# Power_suply.net
KiCad netlist of a schematic drawn in Altium Designer
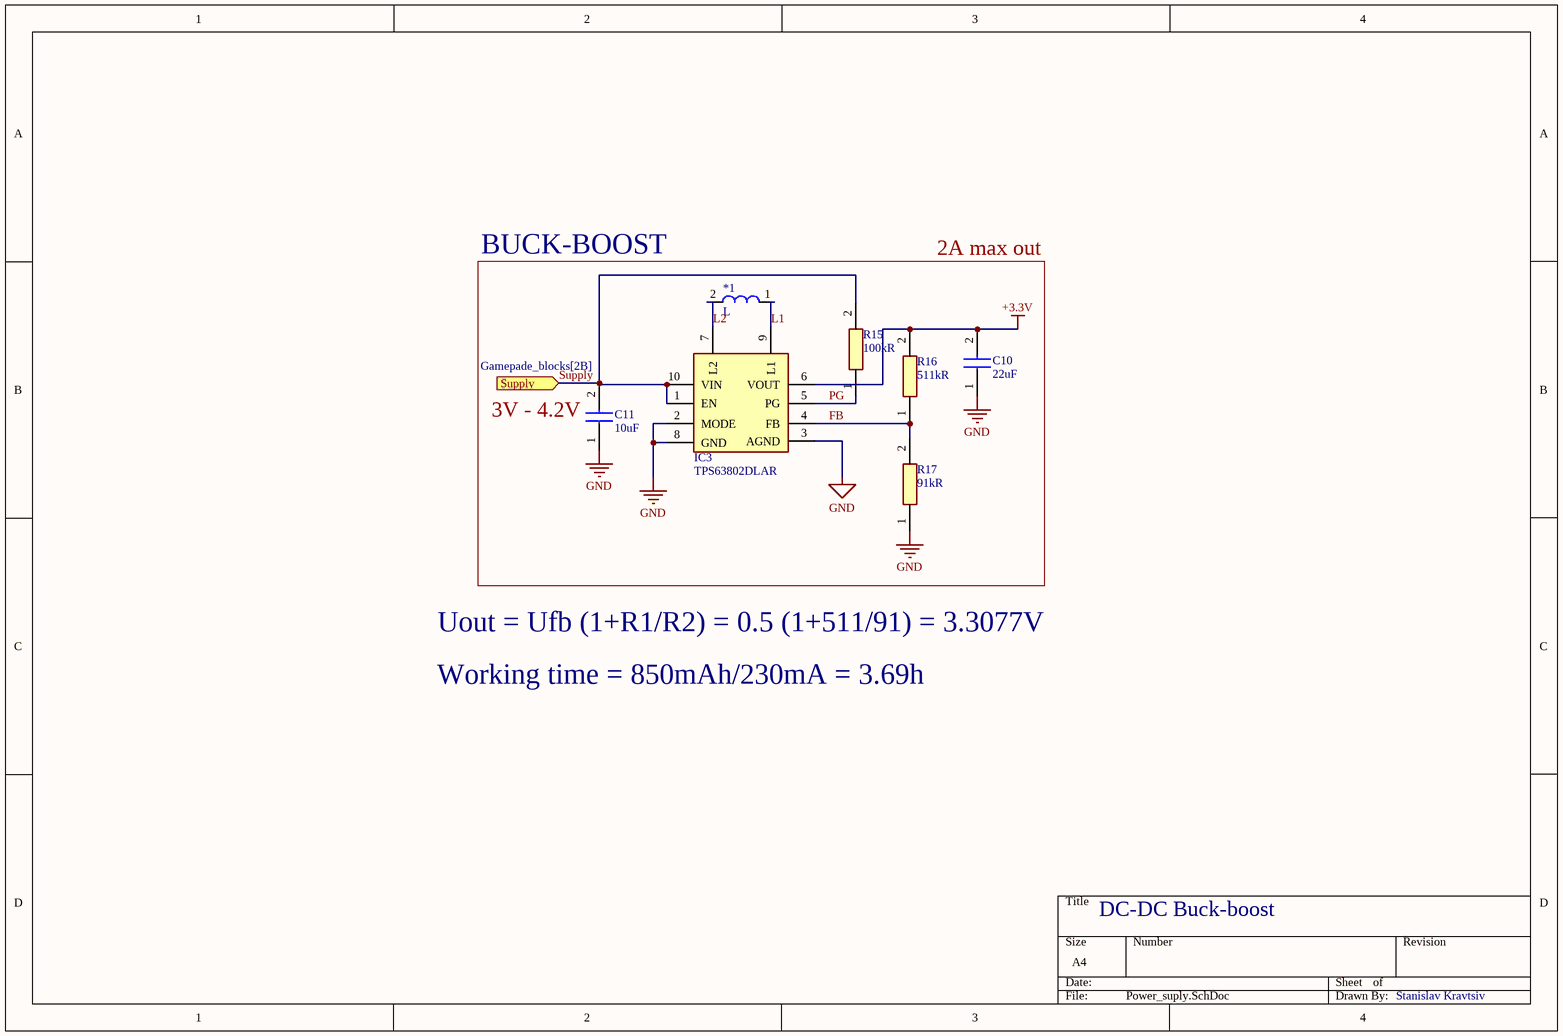
[diagram p0: Power_suply.SchDoc]

(export (version "E")
  (design (tool "Eeschema 10.0.6"))
  (components
    (comp (ref "*1") (value "L") (footprint "Coil") (libsource (lib "Gamepad_schem_lib") (part "L")))
    (comp (ref "C10")
      (value "22uF")
      (footprint "SamacSys:ZRB18x")
      (description "Capacitor")
      (fields
        (field (name "MANUFACTURER_PART_NUMBER") "ZRB18AR61A226ME01L")
        (field (name "MOUSER PART NUMBER") "81-ZRB18AR61A226ME1L")
      )
      (libsource (lib "*") (part "ZRB18AR61A226ME01L"))
    )
    (comp (ref "C11")
      (value "10uF")
      (footprint "SamacSys:CAPC2012X140N")
      (description "Capacitor")
      (fields
        (field (name "MANUFACTURER_PART_NUMBER") "CL21B106KPQNNNG")
        (field (name "MOUSER PART NUMBER") "187-CL21B106KPQNNNG")
      )
      (libsource (lib "*") (part "CL21B106KPQNNNG"))
    )
    (comp (ref "IC3")
      (value "TPS63802DLAR")
      (footprint "SamacSys:TPS63802DLAR")
      (description "Integrated Circuit")
      (fields (field (name "MOUSER PART NUMBER") "595-TPS63802DLAR"))
      (libsource (lib "Gamepad_schem_lib") (part "TPS63802DLAR"))
    )
    (comp (ref "R15")
      (value "100kR")
      (footprint "SamacSys:RESC1608X55N")
      (description "Resistor")
      (fields
        (field (name "MANUFACTURER_PART_NUMBER") "RC0603FR-07100KL")
        (field (name "MOUSER PART NUMBER") "603-RC0603FR-07100KL")
      )
      (libsource (lib "SamacSys") (part "RC0603FR-07100KL"))
    )
    (comp (ref "R16")
      (value "511kR")
      (footprint "SamacSys:RESC1608X55N")
      (description "Resistor")
      (fields
        (field (name "MANUFACTURER_PART_NUMBER") "ERJ-3EKF5113V")
        (field (name "MOUSER PART NUMBER") "667-ERJ-3EKF5113V")
      )
      (libsource (lib "*") (part "ERJ-3EKF5113V"))
    )
    (comp (ref "R17")
      (value "91kR")
      (footprint "SamacSys:RESC1608X55N")
      (description "Resistor")
      (fields
        (field (name "MANUFACTURER_PART_NUMBER") "ERJ-3EKF9102V")
        (field (name "MOUSER PART NUMBER") "667-ERJ-3EKF9102V")
      )
      (libsource (lib "*") (part "ERJ-3EKF9102V"))
    )
  )
  (nets
    (net (code "1") (name "+3.3V") (class "Default")
      (node (ref "C10") (pin "2") (pinfunction "2_2") (pintype "passive"))
      (node (ref "IC3") (pin "6") (pinfunction "VOUT_6") (pintype "passive"))
      (node (ref "R16") (pin "2") (pinfunction "2_2") (pintype "passive"))
    )
    (net (code "2") (name "/FB") (class "Default")
      (node (ref "IC3") (pin "4") (pinfunction "FB_4") (pintype "passive"))
      (node (ref "R16") (pin "1") (pinfunction "1_1") (pintype "passive"))
      (node (ref "R17") (pin "2") (pinfunction "2_2") (pintype "passive"))
    )
    (net (code "3") (name "/L1") (class "Default")
      (node (ref "*1") (pin "1") (pinfunction "17_1") (pintype "passive"))
      (node (ref "IC3") (pin "9") (pinfunction "L1_9") (pintype "passive"))
    )
    (net (code "4") (name "/L2") (class "Default")
      (node (ref "*1") (pin "2") (pinfunction "18_2") (pintype "passive"))
      (node (ref "IC3") (pin "7") (pinfunction "L2_7") (pintype "passive"))
    )
    (net (code "5") (name "/PG") (class "Default")
      (node (ref "IC3") (pin "5") (pinfunction "PG_5") (pintype "passive"))
      (node (ref "R15") (pin "1") (pinfunction "1_1") (pintype "passive"))
    )
    (net (code "6") (name "/Supply") (class "Default")
      (node (ref "C11") (pin "2") (pinfunction "2_2") (pintype "passive"))
      (node (ref "IC3") (pin "1") (pinfunction "EN_1") (pintype "passive"))
      (node (ref "IC3") (pin "10") (pinfunction "VIN_10") (pintype "passive"))
      (node (ref "R15") (pin "2") (pinfunction "2_2") (pintype "passive"))
    )
    (net (code "7") (name "GND") (class "Default")
      (node (ref "C10") (pin "1") (pinfunction "1_1") (pintype "passive"))
      (node (ref "C11") (pin "1") (pinfunction "1_1") (pintype "passive"))
      (node (ref "IC3") (pin "2") (pinfunction "MODE_2") (pintype "passive"))
      (node (ref "IC3") (pin "3") (pinfunction "AGND_3") (pintype "passive"))
      (node (ref "IC3") (pin "8") (pinfunction "GND_8") (pintype "passive"))
      (node (ref "R17") (pin "1") (pinfunction "1_1") (pintype "passive"))
    )
  )
)
